# zxld381-boost-driver-24mm-driver-mk-1.net
KiCad netlist of a schematic drawn in EAGLE
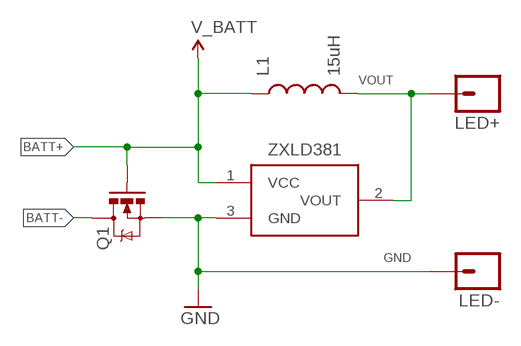
[diagram p0: schematic, sheet 1]

(export (version "E")
  (design (tool "Eeschema 10.0.6"))
  (components
    (comp (ref "L1")
      (value "15uH")
      (footprint "eagle-import:0805")
      (libsource (lib "eagle-import") (part "INDUCTOR0805"))
    )
    (comp (ref "LED+")
      (value "M01PTH-1.2MM-NS")
      (footprint "eagle-import:1X01-1.2MM-NS")
      (libsource (lib "eagle-import") (part "M01PTH-1.2MM-NS"))
    )
    (comp (ref "LED-")
      (value "M01PTH-1.2MM-NS")
      (footprint "eagle-import:1X01-1.2MM-NS")
      (libsource (lib "eagle-import") (part "M01PTH-1.2MM-NS"))
    )
    (comp (ref "Q1")
      (value "MOSFET-NCHANNELIRLML2502")
      (footprint "eagle-import:SOT23")
      (libsource (lib "eagle-import") (part "MOSFET-NCHANNELIRLML2502"))
    )
    (comp (ref "ZXLD381")
      (value "ZXLD381")
      (footprint "eagle-import:SOT23-3")
      (libsource (lib "eagle-import") (part "ZXLD381"))
    )
  )
  (nets
    (net (code "1") (name "/VOUT") (class "Default")
      (node (ref "L1") (pin "2") (pinfunction "2_2") (pintype "passive"))
      (node (ref "LED+") (pin "P$1") (pinfunction "1_P$1") (pintype "passive"))
      (node (ref "ZXLD381") (pin "2") (pinfunction "VOUT_2") (pintype "bidirectional"))
    )
    (net (code "2") (name "BATT+") (class "Default")
      (node (ref "L1") (pin "1") (pinfunction "1_1") (pintype "passive"))
      (node (ref "Q1") (pin "1") (pinfunction "G_1") (pintype "passive"))
      (node (ref "ZXLD381") (pin "1") (pinfunction "VCC_1") (pintype "bidirectional"))
    )
    (net (code "3") (name "BATT-") (class "Default")
      (node (ref "Q1") (pin "3") (pinfunction "D_3") (pintype "passive"))
    )
    (net (code "4") (name "GND") (class "Default")
      (node (ref "LED-") (pin "P$1") (pinfunction "1_P$1") (pintype "passive"))
      (node (ref "Q1") (pin "2") (pinfunction "S_2") (pintype "passive"))
      (node (ref "ZXLD381") (pin "3") (pinfunction "GND_3") (pintype "bidirectional"))
    )
  )
)
